# ScreenCircuitV0_1.net
KiCad netlist of a schematic drawn in EAGLE
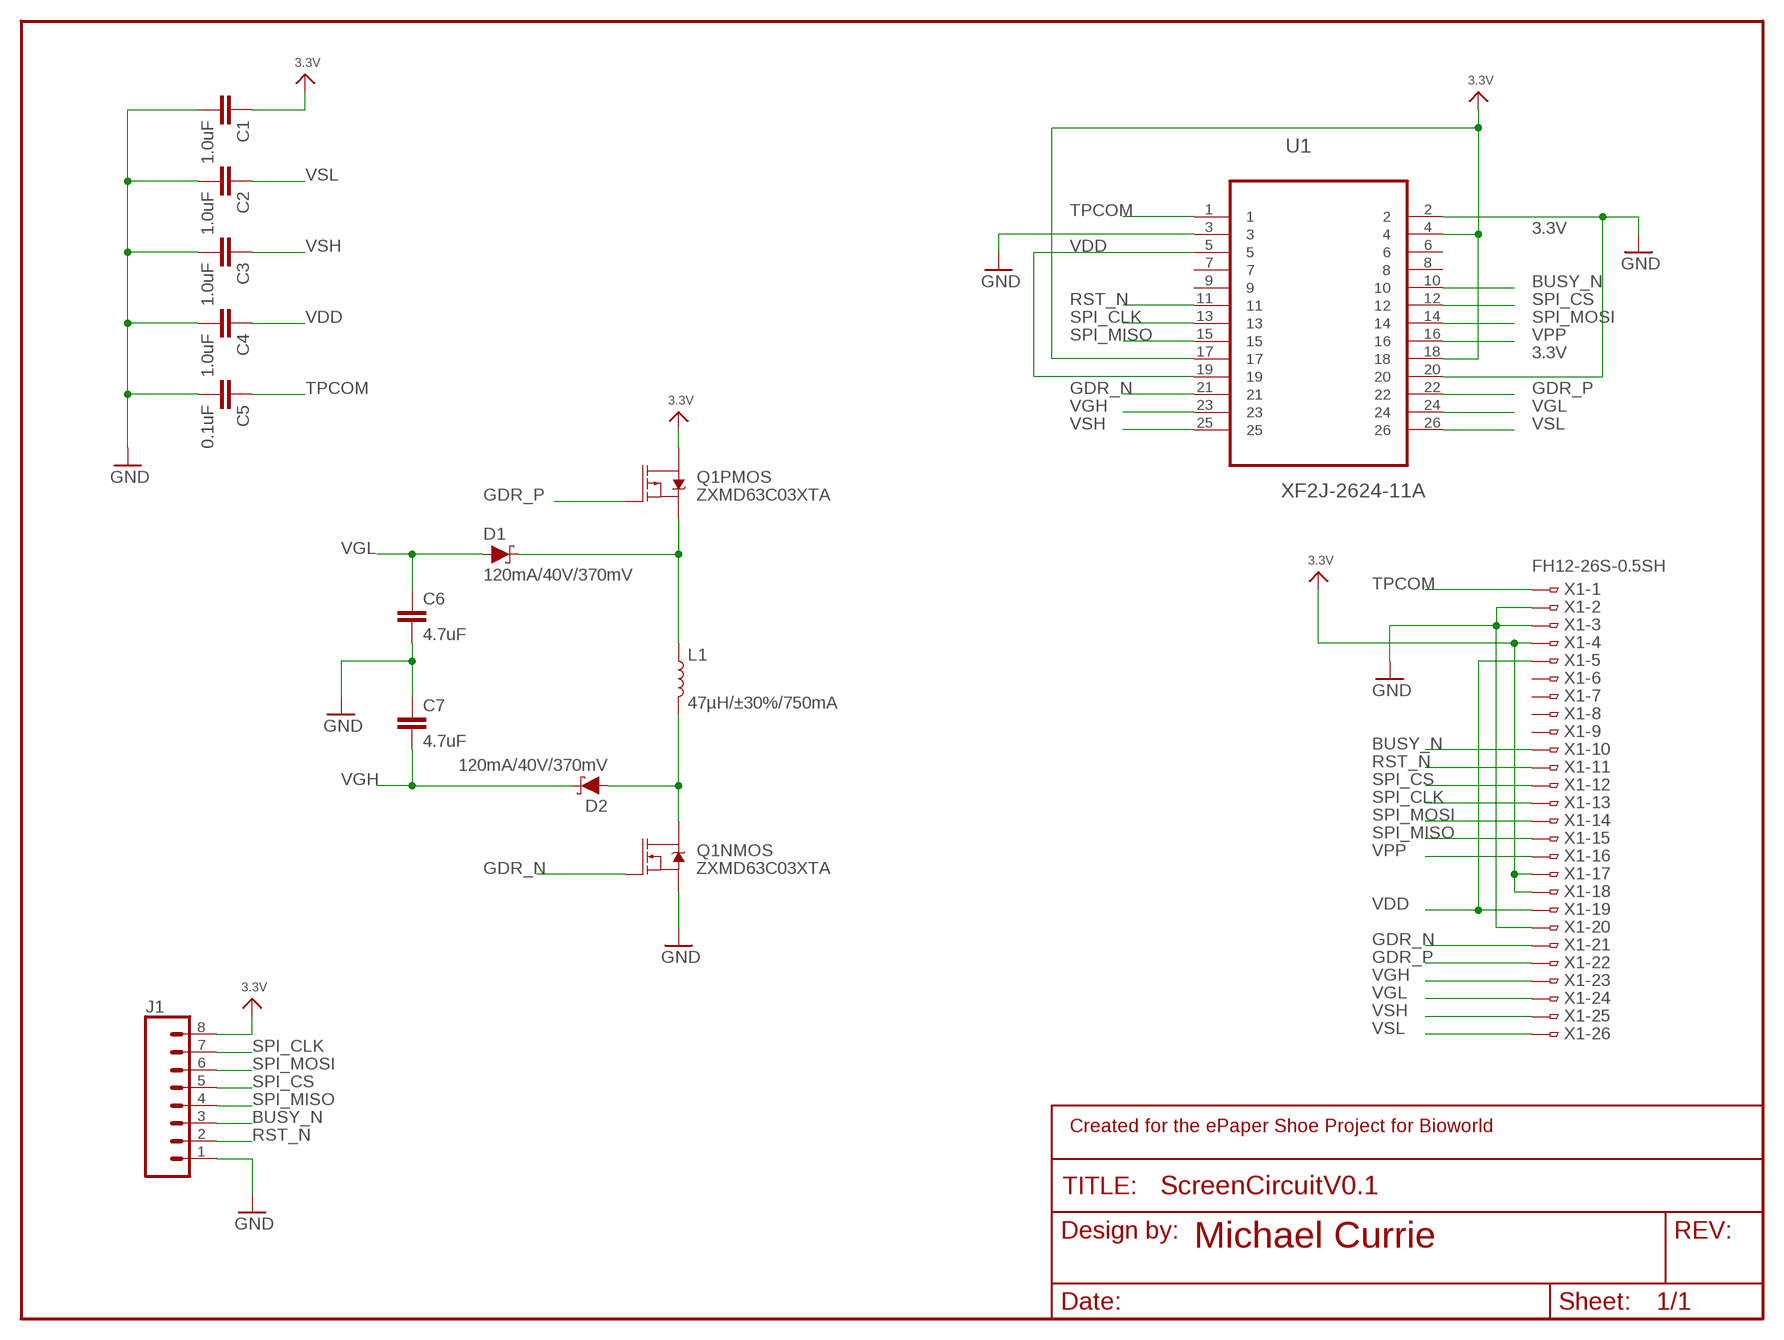
[diagram p0: schematic, sheet 1]

(export (version "E")
  (design (tool "Eeschema 10.0.6"))
  (components
    (comp (ref "C1")
      (value "1.0uF")
      (footprint "eagle-import:1206")
      (libsource (lib "eagle-import") (part "1.0UF-1206-50V-10%"))
    )
    (comp (ref "C2")
      (value "1.0uF")
      (footprint "eagle-import:1206")
      (libsource (lib "eagle-import") (part "1.0UF-1206-50V-10%"))
    )
    (comp (ref "C3")
      (value "1.0uF")
      (footprint "eagle-import:1206")
      (libsource (lib "eagle-import") (part "1.0UF-1206-50V-10%"))
    )
    (comp (ref "C4")
      (value "1.0uF")
      (footprint "eagle-import:1206")
      (libsource (lib "eagle-import") (part "1.0UF-1206-50V-10%"))
    )
    (comp (ref "C5")
      (value "0.1uF")
      (footprint "eagle-import:0603")
      (libsource (lib "eagle-import") (part "0.1UF-0603-100V-10%"))
    )
    (comp (ref "C6")
      (value "4.7uF")
      (footprint "eagle-import:1206")
      (libsource (lib "eagle-import") (part "4.7UF-1206-16V-(+80/-20%)"))
    )
    (comp (ref "C7")
      (value "4.7uF")
      (footprint "eagle-import:1206")
      (libsource (lib "eagle-import") (part "4.7UF-1206-16V-(+80/-20%)"))
    )
    (comp (ref "D1")
      (value "120mA/40V/370mV")
      (footprint "eagle-import:SOD-523")
      (libsource (lib "eagle-import") (part "DIODE-SCHOTTKY-RB751S40"))
    )
    (comp (ref "D2")
      (value "120mA/40V/370mV")
      (footprint "eagle-import:SOD-523")
      (libsource (lib "eagle-import") (part "DIODE-SCHOTTKY-RB751S40"))
    )
    (comp (ref "FRAME1")
      (value "FRAME-LETTER-MICHAELNO_PACKAGE")
      (footprint "eagle-import:DUMMY")
      (fields (field (name "DESIGNER") "Nobody"))
      (libsource (lib "eagle-import") (part "FRAME-LETTER-MICHAELNO_PACKAGE"))
    )
    (comp (ref "J1")
      (value "CONN_08\"")
      (footprint "eagle-import:1X08")
      (libsource (lib "eagle-import") (part "CONN_08{dblquote}"))
    )
    (comp (ref "L1")
      (value "47µH/±30%/750mA")
      (footprint "eagle-import:CR54")
      (libsource (lib "eagle-import") (part "INDUCTOR-CR54-47UH"))
    )
    (comp (ref "Q1")
      (value "IRF7509")
      (footprint "eagle-import:MSOP8")
      (libsource (lib "eagle-import") (part "IRF7509"))
    )
    (comp (ref "U1")
      (value "XF2J-2624-11A")
      (footprint "eagle-import:OMRON_XF2J-2624-11A")
      (libsource (lib "eagle-import") (part "XF2J-2624-11A"))
    )
    (comp (ref "X1")
      (value "FH12-26S-0.5SH")
      (footprint "eagle-import:FH12-26S-0.5SH")
      (fields (field (name "MPN") "FH12-26S-0.5SH(55)"))
      (libsource (lib "eagle-import") (part "FH12-26S-0.5SH"))
    )
  )
  (nets
    (net (code "1") (name "/BUSY_N") (class "Default")
      (node (ref "J1") (pin "3") (pinfunction "3_3") (pintype "passive"))
      (node (ref "U1") (pin "10") (pinfunction "10_10") (pintype "passive"))
      (node (ref "X1") (pin "10") (pinfunction "1_10") (pintype "passive"))
    )
    (net (code "2") (name "/GDR_N") (class "Default")
      (node (ref "Q1") (pin "2") (pinfunction "G_2") (pintype "bidirectional"))
      (node (ref "U1") (pin "21") (pinfunction "21_21") (pintype "passive"))
      (node (ref "X1") (pin "21") (pinfunction "1_21") (pintype "passive"))
    )
    (net (code "3") (name "/GDR_P") (class "Default")
      (node (ref "Q1") (pin "4") (pinfunction "G_4") (pintype "bidirectional"))
      (node (ref "U1") (pin "22") (pinfunction "22_22") (pintype "passive"))
      (node (ref "X1") (pin "22") (pinfunction "1_22") (pintype "passive"))
    )
    (net (code "4") (name "/RST_N") (class "Default")
      (node (ref "J1") (pin "2") (pinfunction "2_2") (pintype "passive"))
      (node (ref "U1") (pin "11") (pinfunction "11_11") (pintype "passive"))
      (node (ref "X1") (pin "11") (pinfunction "1_11") (pintype "passive"))
    )
    (net (code "5") (name "/SPI_CLK") (class "Default")
      (node (ref "J1") (pin "7") (pinfunction "7_7") (pintype "passive"))
      (node (ref "U1") (pin "13") (pinfunction "13_13") (pintype "passive"))
      (node (ref "X1") (pin "13") (pinfunction "1_13") (pintype "passive"))
    )
    (net (code "6") (name "/SPI_CS") (class "Default")
      (node (ref "J1") (pin "5") (pinfunction "5_5") (pintype "passive"))
      (node (ref "U1") (pin "12") (pinfunction "12_12") (pintype "passive"))
      (node (ref "X1") (pin "12") (pinfunction "1_12") (pintype "passive"))
    )
    (net (code "7") (name "/SPI_MISO") (class "Default")
      (node (ref "J1") (pin "4") (pinfunction "4_4") (pintype "passive"))
      (node (ref "U1") (pin "15") (pinfunction "15_15") (pintype "passive"))
      (node (ref "X1") (pin "15") (pinfunction "1_15") (pintype "passive"))
    )
    (net (code "8") (name "/SPI_MOSI") (class "Default")
      (node (ref "J1") (pin "6") (pinfunction "6_6") (pintype "passive"))
      (node (ref "U1") (pin "14") (pinfunction "14_14") (pintype "passive"))
      (node (ref "X1") (pin "14") (pinfunction "1_14") (pintype "passive"))
    )
    (net (code "9") (name "/TPCOM") (class "Default")
      (node (ref "C5") (pin "1") (pinfunction "1_1") (pintype "passive"))
      (node (ref "U1") (pin "1") (pinfunction "1_1") (pintype "passive"))
      (node (ref "X1") (pin "1") (pinfunction "1_1") (pintype "passive"))
    )
    (net (code "10") (name "/VDD") (class "Default")
      (node (ref "C4") (pin "1") (pinfunction "1_1") (pintype "passive"))
      (node (ref "U1") (pin "19") (pinfunction "19_19") (pintype "passive"))
      (node (ref "U1") (pin "5") (pinfunction "5_5") (pintype "passive"))
      (node (ref "X1") (pin "19") (pinfunction "1_19") (pintype "passive"))
      (node (ref "X1") (pin "5") (pinfunction "1_5") (pintype "passive"))
    )
    (net (code "11") (name "/VGH") (class "Default")
      (node (ref "C7") (pin "2") (pinfunction "2_2") (pintype "passive"))
      (node (ref "D2") (pin "C") (pinfunction "C_C") (pintype "passive"))
      (node (ref "U1") (pin "23") (pinfunction "23_23") (pintype "passive"))
      (node (ref "X1") (pin "23") (pinfunction "1_23") (pintype "passive"))
    )
    (net (code "12") (name "/VGL") (class "Default")
      (node (ref "C6") (pin "1") (pinfunction "1_1") (pintype "passive"))
      (node (ref "D1") (pin "A") (pinfunction "A_A") (pintype "passive"))
      (node (ref "U1") (pin "24") (pinfunction "24_24") (pintype "passive"))
      (node (ref "X1") (pin "24") (pinfunction "1_24") (pintype "passive"))
    )
    (net (code "13") (name "/VPP") (class "Default")
      (node (ref "U1") (pin "16") (pinfunction "16_16") (pintype "passive"))
      (node (ref "X1") (pin "16") (pinfunction "1_16") (pintype "passive"))
    )
    (net (code "14") (name "/VSH") (class "Default")
      (node (ref "C3") (pin "1") (pinfunction "1_1") (pintype "passive"))
      (node (ref "U1") (pin "25") (pinfunction "25_25") (pintype "passive"))
      (node (ref "X1") (pin "25") (pinfunction "1_25") (pintype "passive"))
    )
    (net (code "15") (name "/VSL") (class "Default")
      (node (ref "C2") (pin "1") (pinfunction "1_1") (pintype "passive"))
      (node (ref "U1") (pin "26") (pinfunction "26_26") (pintype "passive"))
      (node (ref "X1") (pin "26") (pinfunction "1_26") (pintype "passive"))
    )
    (net (code "16") (name "3.3V") (class "Default")
      (node (ref "C1") (pin "1") (pinfunction "1_1") (pintype "passive"))
      (node (ref "J1") (pin "8") (pinfunction "8_8") (pintype "passive"))
      (node (ref "Q1") (pin "5") (pinfunction "D_5") (pintype "bidirectional"))
      (node (ref "Q1") (pin "6") (pinfunction "D_6") (pintype "bidirectional"))
      (node (ref "U1") (pin "17") (pinfunction "17_17") (pintype "passive"))
      (node (ref "U1") (pin "18") (pinfunction "18_18") (pintype "passive"))
      (node (ref "U1") (pin "4") (pinfunction "4_4") (pintype "passive"))
      (node (ref "X1") (pin "17") (pinfunction "1_17") (pintype "passive"))
      (node (ref "X1") (pin "18") (pinfunction "1_18") (pintype "passive"))
      (node (ref "X1") (pin "4") (pinfunction "1_4") (pintype "passive"))
    )
    (net (code "17") (name "GND") (class "Default")
      (node (ref "C1") (pin "2") (pinfunction "2_2") (pintype "passive"))
      (node (ref "C2") (pin "2") (pinfunction "2_2") (pintype "passive"))
      (node (ref "C3") (pin "2") (pinfunction "2_2") (pintype "passive"))
      (node (ref "C4") (pin "2") (pinfunction "2_2") (pintype "passive"))
      (node (ref "C5") (pin "2") (pinfunction "2_2") (pintype "passive"))
      (node (ref "C6") (pin "2") (pinfunction "2_2") (pintype "passive"))
      (node (ref "C7") (pin "1") (pinfunction "1_1") (pintype "passive"))
      (node (ref "J1") (pin "1") (pinfunction "1_1") (pintype "passive"))
      (node (ref "Q1") (pin "1") (pinfunction "S_1") (pintype "bidirectional"))
      (node (ref "U1") (pin "2") (pinfunction "2_2") (pintype "passive"))
      (node (ref "U1") (pin "20") (pinfunction "20_20") (pintype "passive"))
      (node (ref "U1") (pin "3") (pinfunction "3_3") (pintype "passive"))
      (node (ref "X1") (pin "2") (pinfunction "1_2") (pintype "passive"))
      (node (ref "X1") (pin "20") (pinfunction "1_20") (pintype "passive"))
      (node (ref "X1") (pin "3") (pinfunction "1_3") (pintype "passive"))
    )
    (net (code "18") (name "Net-(L1-1)") (class "Default")
      (node (ref "D1") (pin "C") (pinfunction "C_C") (pintype "passive"))
      (node (ref "L1") (pin "P$1") (pinfunction "1_P$1") (pintype "passive"))
      (node (ref "Q1") (pin "3") (pinfunction "S_3") (pintype "bidirectional"))
    )
    (net (code "19") (name "Net-(L1-2)") (class "Default")
      (node (ref "D2") (pin "A") (pinfunction "A_A") (pintype "passive"))
      (node (ref "L1") (pin "P$2") (pinfunction "2_P$2") (pintype "passive"))
      (node (ref "Q1") (pin "7") (pinfunction "D_7") (pintype "bidirectional"))
      (node (ref "Q1") (pin "8") (pinfunction "D_8") (pintype "bidirectional"))
    )
    (net (code "20") (name "unconnected-(U1-Pad6)") (class "Default")
      (node (ref "U1") (pin "6") (pinfunction "6_6") (pintype "passive"))
    )
    (net (code "21") (name "unconnected-(U1-Pad7)") (class "Default")
      (node (ref "U1") (pin "7") (pinfunction "7_7") (pintype "passive"))
    )
    (net (code "22") (name "unconnected-(U1-Pad8)") (class "Default")
      (node (ref "U1") (pin "8") (pinfunction "8_8") (pintype "passive"))
    )
    (net (code "23") (name "unconnected-(U1-Pad9)") (class "Default")
      (node (ref "U1") (pin "9") (pinfunction "9_9") (pintype "passive"))
    )
    (net (code "24") (name "unconnected-(X1W-1-Pad6)") (class "Default")
      (node (ref "X1") (pin "6") (pinfunction "1_6") (pintype "passive"))
    )
    (net (code "25") (name "unconnected-(X1X-1-Pad7)") (class "Default")
      (node (ref "X1") (pin "7") (pinfunction "1_7") (pintype "passive"))
    )
    (net (code "26") (name "unconnected-(X1Y-1-Pad8)") (class "Default")
      (node (ref "X1") (pin "8") (pinfunction "1_8") (pintype "passive"))
    )
    (net (code "27") (name "unconnected-(X1Z-1-Pad9)") (class "Default")
      (node (ref "X1") (pin "9") (pinfunction "1_9") (pintype "passive"))
    )
  )
)
